# Y.net
KiCad netlist of a schematic drawn in Altium Designer
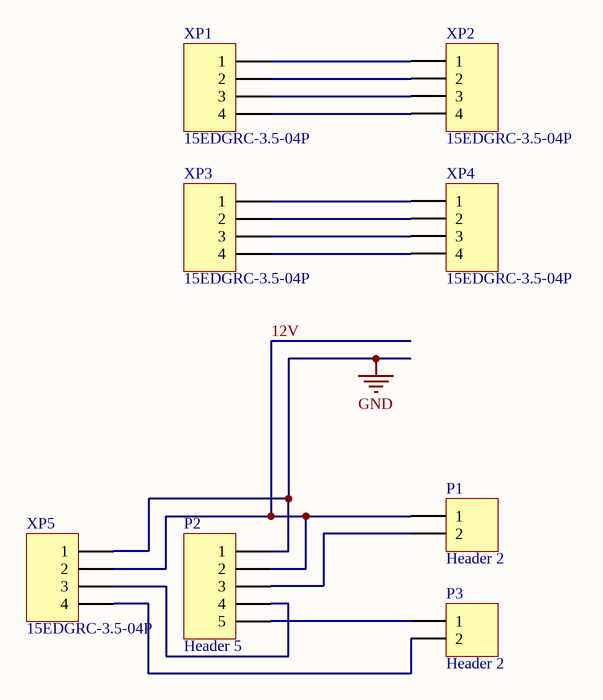
[diagram p0: Y.SchDoc]

(export (version "E")
  (design (tool "Eeschema 10.0.6"))
  (components
    (comp (ref "P1")
      (value "Header 2")
      (footprint "HDR1X2")
      (description "Header, 2-Pin")
      (fields (field (name "PUBLISHER") "Altium Limited"))
      (libsource (lib "Miscellaneous Connectors") (part "Header 2"))
    )
    (comp (ref "P2")
      (value "Header 5")
      (footprint "HDR1X5")
      (description "Header, 5-Pin")
      (fields (field (name "PUBLISHER") "Altium Limited"))
      (libsource (lib "Miscellaneous Connectors") (part "Header 5"))
    )
    (comp (ref "P3")
      (value "Header 2")
      (footprint "HDR1X2")
      (description "Header, 2-Pin")
      (fields (field (name "PUBLISHER") "Altium Limited"))
      (libsource (lib "Miscellaneous Connectors") (part "Header 2"))
    )
    (comp (ref "XP1")
      (value "15EDGRC-3.5-04P")
      (footprint "RR_CONN_15EDGRC-3.5-04P")
      (description "CONN 15EDGRC-3.5-04P R-HEADER")
      (fields (field (name "MANUFACTURER") "DEGSON ELECTRONICS"))
      (libsource (lib "") (part "15EDGRC-3.5-04P_1"))
    )
    (comp (ref "XP2")
      (value "15EDGRC-3.5-04P")
      (footprint "RR_CONN_15EDGRC-3.5-04P")
      (description "CONN 15EDGRC-3.5-04P R-HEADER")
      (fields (field (name "MANUFACTURER") "DEGSON ELECTRONICS"))
      (libsource (lib "RozumLibrary") (part "15EDGRC-3.5-04P"))
    )
    (comp (ref "XP3")
      (value "15EDGRC-3.5-04P")
      (footprint "RR_CONN_15EDGRC-3.5-04P")
      (description "CONN 15EDGRC-3.5-04P R-HEADER")
      (fields (field (name "MANUFACTURER") "DEGSON ELECTRONICS"))
      (libsource (lib "") (part "15EDGRC-3.5-04P_1"))
    )
    (comp (ref "XP4")
      (value "15EDGRC-3.5-04P")
      (footprint "RR_CONN_15EDGRC-3.5-04P")
      (description "CONN 15EDGRC-3.5-04P R-HEADER")
      (fields (field (name "MANUFACTURER") "DEGSON ELECTRONICS"))
      (libsource (lib "RozumLibrary") (part "15EDGRC-3.5-04P"))
    )
    (comp (ref "XP5")
      (value "15EDGRC-3.5-04P")
      (footprint "RR_CONN_15EDGRC-3.5-04P")
      (description "CONN 15EDGRC-3.5-04P R-HEADER")
      (fields (field (name "MANUFACTURER") "DEGSON ELECTRONICS"))
      (libsource (lib "") (part "15EDGRC-3.5-04P_1"))
    )
  )
  (nets
    (net (code "1") (name "/12V") (class "Default")
      (node (ref "P1") (pin "1") (pinfunction "1_1") (pintype "passive"))
      (node (ref "P2") (pin "2") (pinfunction "2_2") (pintype "passive"))
      (node (ref "XP5") (pin "2") (pinfunction "2_2") (pintype "passive"))
    )
    (net (code "2") (name "GND") (class "Default")
      (node (ref "P2") (pin "1") (pinfunction "1_1") (pintype "passive"))
      (node (ref "XP5") (pin "1") (pinfunction "1_1") (pintype "passive"))
    )
    (net (code "3") (name "Net-(P1-Pad2)") (class "Default")
      (node (ref "P1") (pin "2") (pinfunction "2_2") (pintype "passive"))
      (node (ref "P2") (pin "3") (pinfunction "3_3") (pintype "passive"))
    )
    (net (code "4") (name "Net-(P2-Pad4)") (class "Default")
      (node (ref "P2") (pin "4") (pinfunction "4_4") (pintype "passive"))
      (node (ref "XP5") (pin "3") (pinfunction "3_3") (pintype "passive"))
    )
    (net (code "5") (name "Net-(P2-Pad5)") (class "Default")
      (node (ref "P2") (pin "5") (pinfunction "5_5") (pintype "passive"))
      (node (ref "P3") (pin "1") (pinfunction "1_1") (pintype "passive"))
    )
    (net (code "6") (name "Net-(P3-Pad2)") (class "Default")
      (node (ref "P3") (pin "2") (pinfunction "2_2") (pintype "passive"))
      (node (ref "XP5") (pin "4") (pinfunction "4_4") (pintype "passive"))
    )
    (net (code "7") (name "Net-(XP1-Pad1)") (class "Default")
      (node (ref "XP1") (pin "1") (pinfunction "1_1") (pintype "passive"))
      (node (ref "XP2") (pin "1") (pinfunction "1_1") (pintype "passive"))
    )
    (net (code "8") (name "Net-(XP1-Pad2)") (class "Default")
      (node (ref "XP1") (pin "2") (pinfunction "2_2") (pintype "passive"))
      (node (ref "XP2") (pin "2") (pinfunction "2_2") (pintype "passive"))
    )
    (net (code "9") (name "Net-(XP1-Pad3)") (class "Default")
      (node (ref "XP1") (pin "3") (pinfunction "3_3") (pintype "passive"))
      (node (ref "XP2") (pin "3") (pinfunction "3_3") (pintype "passive"))
    )
    (net (code "10") (name "Net-(XP1-Pad4)") (class "Default")
      (node (ref "XP1") (pin "4") (pinfunction "4_4") (pintype "passive"))
      (node (ref "XP2") (pin "4") (pinfunction "4_4") (pintype "passive"))
    )
    (net (code "11") (name "Net-(XP3-Pad1)") (class "Default")
      (node (ref "XP3") (pin "1") (pinfunction "1_1") (pintype "passive"))
      (node (ref "XP4") (pin "1") (pinfunction "1_1") (pintype "passive"))
    )
    (net (code "12") (name "Net-(XP3-Pad2)") (class "Default")
      (node (ref "XP3") (pin "2") (pinfunction "2_2") (pintype "passive"))
      (node (ref "XP4") (pin "2") (pinfunction "2_2") (pintype "passive"))
    )
    (net (code "13") (name "Net-(XP3-Pad3)") (class "Default")
      (node (ref "XP3") (pin "3") (pinfunction "3_3") (pintype "passive"))
      (node (ref "XP4") (pin "3") (pinfunction "3_3") (pintype "passive"))
    )
    (net (code "14") (name "Net-(XP3-Pad4)") (class "Default")
      (node (ref "XP3") (pin "4") (pinfunction "4_4") (pintype "passive"))
      (node (ref "XP4") (pin "4") (pinfunction "4_4") (pintype "passive"))
    )
  )
)
